# power.net
KiCad netlist of a schematic drawn in Altium Designer
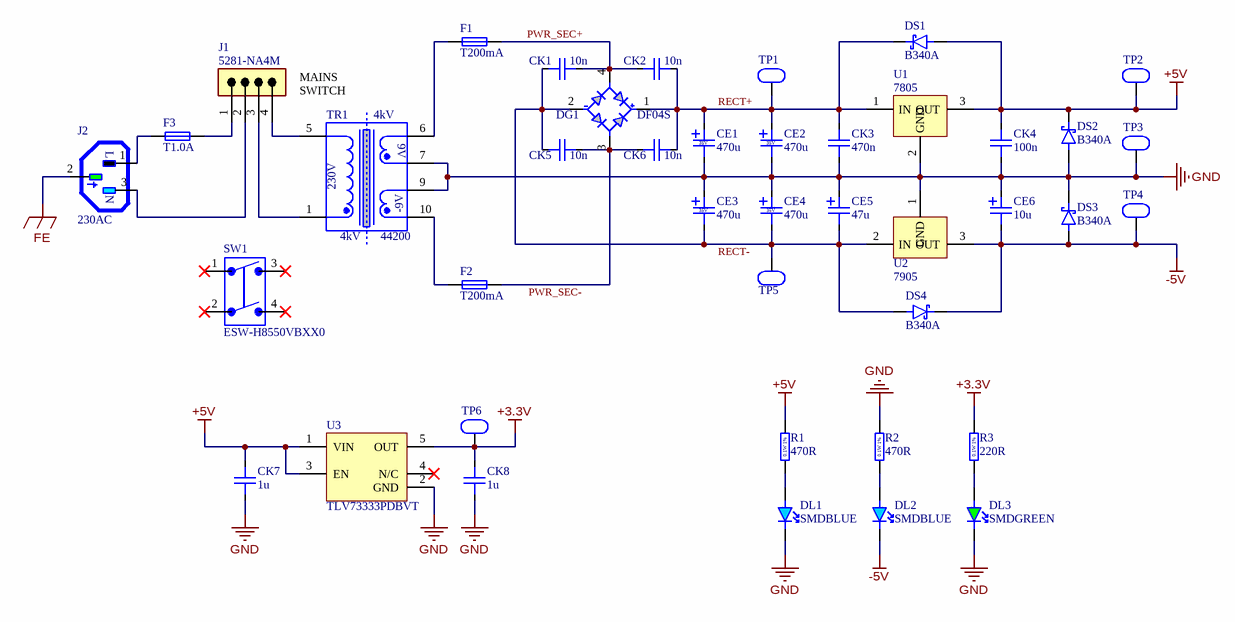
[diagram p0: power.SchDoc]

(export (version "E")
  (design (tool "Eeschema 10.0.6"))
  (components
    (comp (ref "CE1")
      (value "470u")
      (description "C; 470u; 35V; 20%; Aluminum Electrolytic; ??;")
      (fields (field (name "SCH_INFO") "35V"))
      (libsource (lib "") (part "CE_1"))
    )
    (comp (ref "CE2")
      (value "470u")
      (description "C; 470u; 35V; 20%; Aluminum Electrolytic; ??;")
      (fields (field (name "SCH_INFO") "35V"))
      (libsource (lib "") (part "CE_1"))
    )
    (comp (ref "CE3")
      (value "470u")
      (description "C; 470u; 35V; 20%; Aluminum Electrolytic; ??;")
      (fields (field (name "SCH_INFO") "35V"))
      (libsource (lib "") (part "CE_1"))
    )
    (comp (ref "CE4")
      (value "470u")
      (description "C; 470u; 35V; 20%; Aluminum Electrolytic; ??;")
      (fields (field (name "SCH_INFO") "35V"))
      (libsource (lib "") (part "CE_1"))
    )
    (comp (ref "CE5")
      (value "47u")
      (footprint "CAPAE6.8X6.8(D_SIZE)")
      (description "C; 47u; 35V; 20%; Aluminum Electrolytic; ??;")
      (fields (field (name "MANUFACTURER") "Surge, MPN: SVZ21V470M0605V1"))
      (libsource (lib "altium_sql") (part "CE"))
    )
    (comp (ref "CE6")
      (value "10u")
      (footprint "CAPAE5.5X5.5(C_SIZE)")
      (description "C; 10u; 35V; 20%; Aluminum Electrolytic; ??;")
      (fields (field (name "MANUFACTURER") "SAMWHA: SC1V106M05005VR259;;SAMWHA: SC1V106M05005VR289"))
      (libsource (lib "altium_sql") (part "CE"))
    )
    (comp (ref "CK1")
      (value "10n")
      (footprint "CAPC1608X09N(SMC0603)")
      (description "C; 10n; 50V; 5%; NP0/C0G; ??;")
      (fields (field (name "MANUFACTURER") "TDK: C1608C0G1H103J080AA"))
      (libsource (lib "altium_sql") (part "CK"))
    )
    (comp (ref "CK2")
      (value "10n")
      (footprint "CAPC1608X09N(SMC0603)")
      (description "C; 10n; 50V; 5%; NP0/C0G; ??;")
      (fields (field (name "MANUFACTURER") "TDK: C1608C0G1H103J080AA"))
      (libsource (lib "altium_sql") (part "CK"))
    )
    (comp (ref "CK3")
      (value "470n")
      (footprint "CAPC1608X09N(SMC0603)")
      (description "C; 470n; 50V; 10%; X7R; ??;")
      (fields
        (field (name "MANUFACTURER") "TDK: C1608X7R1H474KT-S;;TDK: C1608X7R1H474KT000E;;TDK: C1608X7R1H474K080AC")
      )
      (libsource (lib "altium_sql") (part "CK"))
    )
    (comp (ref "CK4")
      (value "100n")
      (footprint "CAPC1608X09N(SMC0603)")
      (description "C; 100n; 100V; 10%; X7R; ??;")
      (fields
        (field (name "MANUFACTURER") "Murata Electronics: GRM188R72A104KA35D;;Yageo: CC0603KRX7R0BB104")
      )
      (libsource (lib "altium_sql") (part "CK"))
    )
    (comp (ref "CK5")
      (value "10n")
      (footprint "CAPC1608X09N(SMC0603)")
      (description "C; 10n; 50V; 5%; NP0/C0G; ??;")
      (fields (field (name "MANUFACTURER") "TDK: C1608C0G1H103J080AA"))
      (libsource (lib "altium_sql") (part "CK"))
    )
    (comp (ref "CK6")
      (value "10n")
      (footprint "CAPC1608X09N(SMC0603)")
      (description "C; 10n; 50V; 5%; NP0/C0G; ??;")
      (fields (field (name "MANUFACTURER") "TDK: C1608C0G1H103J080AA"))
      (libsource (lib "altium_sql") (part "CK"))
    )
    (comp (ref "CK7")
      (value "1u")
      (footprint "CAPC1608X09N(SMC0603)")
      (description "C; 1u; 50V; 10%; X5R; ??;")
      (libsource (lib "altium_sql") (part "CK"))
    )
    (comp (ref "CK8")
      (value "1u")
      (footprint "CAPC1608X09N(SMC0603)")
      (description "C; 1u; 50V; 10%; X5R; ??;")
      (libsource (lib "altium_sql") (part "CK"))
    )
    (comp (ref "DG1")
      (value "DF04S")
      (footprint "DIP300RM5.08_SMD")
      (description "D; Bridge; 400V; 1A; 1x;")
      (libsource (lib "altium_sql") (part "EDG+DF04SXX0"))
    )
    (comp (ref "DL1")
      (value "SMDBLUE")
      (footprint "DIOC2012X12N(SMLED0805)B")
      (description "Ind; Light; Blue;")
      (fields (field (name "MANUFACTURER") "MULTICOMP: OVS-0803"))
      (libsource (lib "altium_sql") (part "DL_B"))
    )
    (comp (ref "DL2")
      (value "SMDBLUE")
      (footprint "DIOC2012X12N(SMLED0805)B")
      (description "Ind; Light; Blue;")
      (fields (field (name "MANUFACTURER") "MULTICOMP: OVS-0803"))
      (libsource (lib "altium_sql") (part "DL_B"))
    )
    (comp (ref "DL3")
      (value "SMDGREEN")
      (footprint "DIOC2012X12N(SMLED0805)G")
      (description "Ind; Light; Green;")
      (fields (field (name "MANUFACTURER") "HEBEI: 0805KGCT;;BRIGHTLED: BL-HGE35A-AV-TRB"))
      (libsource (lib "altium_sql") (part "DL_G"))
    )
    (comp (ref "DS1")
      (value "B340A")
      (footprint "DIOM5127X23N(SMA)")
      (description "D; Schottky; 40V; 3A; 1x;")
      (fields
        (field (name "MANUFACTURER") "DIODES INC: B340A-13-F;;ONS: MBRA340T3G;;VISHAY: SSA34;;BOURNS: B340LF;;MCC: SK34A-LTP")
      )
      (libsource (lib "altium_sql") (part "DS"))
    )
    (comp (ref "DS2")
      (value "B340A")
      (footprint "DIOM5127X23N(SMA)")
      (description "D; Schottky; 40V; 3A; 1x;")
      (fields
        (field (name "MANUFACTURER") "DIODES INC: B340A-13-F;;ONS: MBRA340T3G;;VISHAY: SSA34;;BOURNS: B340LF;;MCC: SK34A-LTP")
      )
      (libsource (lib "altium_sql") (part "DS"))
    )
    (comp (ref "DS3")
      (value "B340A")
      (footprint "DIOM5127X23N(SMA)")
      (description "D; Schottky; 40V; 3A; 1x;")
      (fields
        (field (name "MANUFACTURER") "DIODES INC: B340A-13-F;;ONS: MBRA340T3G;;VISHAY: SSA34;;BOURNS: B340LF;;MCC: SK34A-LTP")
      )
      (libsource (lib "altium_sql") (part "DS"))
    )
    (comp (ref "DS4")
      (value "B340A")
      (footprint "DIOM5127X23N(SMA)")
      (description "D; Schottky; 40V; 3A; 1x;")
      (fields
        (field (name "MANUFACTURER") "DIODES INC: B340A-13-F;;ONS: MBRA340T3G;;VISHAY: SSA34;;BOURNS: B340LF;;MCC: SK34A-LTP")
      )
      (libsource (lib "altium_sql") (part "DS"))
    )
    (comp (ref "F1")
      (value "T200mA")
      (footprint "FUSE-C8.5")
      (description "CP; Current [A]; 0.2; R:No; 1x;")
      (fields (field (name "MANUFACTURER") "SCHURTER: MST250 0034.6608;;SCHURTER: MST250 0034.6708"))
      (libsource (lib "altium_sql") (part "FUSE_PCB"))
    )
    (comp (ref "F2")
      (value "T200mA")
      (footprint "FUSE-C8.5")
      (description "CP; Current [A]; 0.2; R:No; 1x;")
      (fields (field (name "MANUFACTURER") "SCHURTER: MST250 0034.6608;;SCHURTER: MST250 0034.6708"))
      (libsource (lib "altium_sql") (part "FUSE_PCB"))
    )
    (comp (ref "F3")
      (value "T1.0A")
      (footprint "FUSE-C8.5")
      (description "CP; Current [A]; 1; R:No; 1x;")
      (fields (field (name "MANUFACTURER") "SCHURTER: 34,6615"))
      (libsource (lib "altium_sql") (part "FUSE_PCB"))
    )
    (comp (ref "J1")
      (value "5281-NA4M")
      (footprint "4P-NA-5.08")
      (description "Con; Wire to board RM5.04; 4x; PCB; Straight; 250V; 7A; Male; Tin; ??;")
      (fields
        (field (name "MANUFACTURER") "HSUAN MAO: W4508-04PSYTW0R;;HSM: W4508-04PSYTW0R;;MOLEX: 10-32-1041")
      )
      (libsource (lib "altium_sql") (part "EJ-5281-NA4MX0"))
    )
    (comp (ref "J2")
      (value "230AC")
      (footprint "SCHURTER_GSP1.8501.1")
      (description "Con; AC plug; 1x; PCB; ??; 250V; 10A; Male; Tin; ??;")
      (fields (field (name "MANUFACTURER") "SCHURTER: GSP1.8501.1"))
      (libsource (lib "altium_sql") (part "EJ-GSP1SC1"))
    )
    (comp (ref "R1")
      (value "470R")
      (footprint "RESC1608X06N(SMR0603)")
      (description "R; 470R; 0.1W; 1%; 75V; Thick Film; ±100ppm/K; 1x;")
      (fields
        (field (name "MANUFACTURER") "Yageo: RC0603FR-07470RL;;Panasonic: ERJ3EKF4700V")
        (field (name "SCH_INFO") "0.1W 1%")
      )
      (libsource (lib "altium_sql") (part "R"))
    )
    (comp (ref "R2")
      (value "470R")
      (footprint "RESC1608X06N(SMR0603)")
      (description "R; 470R; 0.1W; 1%; 75V; Thick Film; ±100ppm/K; 1x;")
      (fields
        (field (name "MANUFACTURER") "Yageo: RC0603FR-07470RL;;Panasonic: ERJ3EKF4700V")
        (field (name "SCH_INFO") "0.1W 1%")
      )
      (libsource (lib "altium_sql") (part "R"))
    )
    (comp (ref "R3")
      (value "220R")
      (footprint "RESC1608X06N(SMR0603)")
      (description "R; 220R; 0.1W; 1%; 75V; Thick Film; ±100ppm/K; 1x;")
      (fields (field (name "MANUFACTURER") "VISHAY: CRCW0603220RFKEA") (field (name "SCH_INFO") "0.1W 1%"))
      (libsource (lib "altium_sql") (part "R"))
    )
    (comp (ref "SW1")
      (value "ESW-H8550VBXX0")
      (description "MSw; DPST; Panel; 2x; DC:??V; DC:??A; AC:250V; AC:9A; CV:??V; Switch;")
      (fields (field (name "MANUFACTURER") "SWITRONIC: R19-20.BBBT;;SWITRONIC: R19-20.BBBT+-G"))
      (libsource (lib "altium_sql") (part "ESW-H8550VBXX0"))
    )
    (comp (ref "TP1")
      (value "Test Point")
      (footprint "SMD_Testpoint_Onelayer")
      (description "Con; Test Point; 1x; PCB; ??; ??V; ??A; ??; Tin; Contact;")
      (fields (field (name "MANUFACTURER") "Harwin: S1751-46R") (field (name "CONNECTOR_PART") "Contact"))
      (libsource (lib "altium_sql") (part "EJ+TESTPOINTXX0"))
    )
    (comp (ref "TP2")
      (value "Test Point")
      (footprint "SMD_Testpoint_Onelayer")
      (description "Con; Test Point; 1x; PCB; ??; ??V; ??A; ??; Tin; Contact;")
      (fields (field (name "MANUFACTURER") "Harwin: S1751-46R") (field (name "CONNECTOR_PART") "Contact"))
      (libsource (lib "altium_sql") (part "EJ+TESTPOINTXX0"))
    )
    (comp (ref "TP3")
      (value "Test Point")
      (footprint "SMD_Testpoint_Onelayer")
      (description "Con; Test Point; 1x; PCB; ??; ??V; ??A; ??; Tin; Contact;")
      (fields (field (name "MANUFACTURER") "Harwin: S1751-46R") (field (name "CONNECTOR_PART") "Contact"))
      (libsource (lib "altium_sql") (part "EJ+TESTPOINTXX0"))
    )
    (comp (ref "TP4")
      (value "Test Point")
      (footprint "SMD_Testpoint_Onelayer")
      (description "Con; Test Point; 1x; PCB; ??; ??V; ??A; ??; Tin; Contact;")
      (fields (field (name "MANUFACTURER") "Harwin: S1751-46R") (field (name "CONNECTOR_PART") "Contact"))
      (libsource (lib "altium_sql") (part "EJ+TESTPOINTXX0"))
    )
    (comp (ref "TP5")
      (value "Test Point")
      (footprint "SMD_Testpoint_Onelayer")
      (description "Con; Test Point; 1x; PCB; ??; ??V; ??A; ??; Tin; Contact;")
      (fields (field (name "MANUFACTURER") "Harwin: S1751-46R") (field (name "CONNECTOR_PART") "Contact"))
      (libsource (lib "altium_sql") (part "EJ+TESTPOINTXX0"))
    )
    (comp (ref "TP6")
      (value "Test Point")
      (footprint "SMD_Testpoint_Onelayer")
      (description "Con; Test Point; 1x; PCB; ??; ??V; ??A; ??; Tin; Contact;")
      (fields (field (name "MANUFACTURER") "Harwin: S1751-46R") (field (name "CONNECTOR_PART") "Contact"))
      (libsource (lib "altium_sql") (part "EJ+TESTPOINTXX0"))
    )
    (comp (ref "TR1")
      (value "44200")
      (footprint "44200")
      (description "Transformer 230V/2x9V, 2x178mA")
      (libsource (lib "custom-footprints") (part "44200"))
    )
    (comp (ref "U1")
      (value "7805")
      (footprint "DPAK254P1544X483-3N(D2PAK)")
      (description "Fixed, Three Terminal Pos  Regulator 5V/1A in D2PAK")
      (libsource (lib "custom-footprints") (part "L7805AC"))
    )
    (comp (ref "U2")
      (value "7905")
      (footprint "DPAK254P1544X483-3N(D2PAK)")
      (description "Fixed, Three Terminal Pos  Regulator -5V/1A in D2PAK")
      (libsource (lib "custom-footprints") (part "L7905AC"))
    )
    (comp (ref "U3")
      (value "TLV73333PDBVT")
      (footprint "SOT95P280X145-5N(SOT23-5)")
      (description "IC; Linear Regulator/Reference; ??V; 5.5V; 1x;")
      (fields (field (name "MANUFACTURER") "Texas Instruments: TLV73333PDBVT"))
      (libsource (lib "altium_sql") (part "EU+NCV8702SN18XX0"))
    )
  )
  (nets
    (net (code "1") (name "+3.3V") (class "Default")
      (node (ref "CK8") (pin "1") (pinfunction "1_1") (pintype "passive"))
      (node (ref "R3") (pin "2") (pinfunction "2_2") (pintype "passive"))
      (node (ref "TP6") (pin "1") (pintype "passive"))
      (node (ref "U3") (pin "5") (pinfunction "OUT_5") (pintype "power_in"))
    )
    (net (code "2") (name "+5V") (class "Default")
      (node (ref "CK4") (pin "1") (pinfunction "1_1") (pintype "passive"))
      (node (ref "CK7") (pin "1") (pinfunction "1_1") (pintype "passive"))
      (node (ref "DS1") (pin "2") (pinfunction "A_2") (pintype "passive"))
      (node (ref "DS2") (pin "1") (pinfunction "C_1") (pintype "passive"))
      (node (ref "R1") (pin "2") (pinfunction "2_2") (pintype "passive"))
      (node (ref "TP2") (pin "1") (pintype "passive"))
      (node (ref "U1") (pin "3") (pinfunction "OUT_3") (pintype "passive"))
      (node (ref "U3") (pin "1") (pinfunction "VIN_1") (pintype "power_in"))
      (node (ref "U3") (pin "3") (pinfunction "EN_3") (pintype "passive"))
    )
    (net (code "3") (name "-5V") (class "Default")
      (node (ref "CE6") (pin "2") (pinfunction "2_2") (pintype "passive"))
      (node (ref "DL2") (pin "1") (pinfunction "C_1") (pintype "passive"))
      (node (ref "DS3") (pin "2") (pinfunction "A_2") (pintype "passive"))
      (node (ref "DS4") (pin "1") (pinfunction "C_1") (pintype "passive"))
      (node (ref "TP4") (pin "1") (pintype "passive"))
      (node (ref "U2") (pin "3") (pinfunction "OUT_3") (pintype "passive"))
    )
    (net (code "4") (name "/PWR_SEC+") (class "Default")
      (node (ref "CK1") (pin "2") (pinfunction "2_2") (pintype "passive"))
      (node (ref "CK2") (pin "1") (pinfunction "1_1") (pintype "passive"))
      (node (ref "DG1") (pin "4") (pinfunction "AC_4") (pintype "passive"))
      (node (ref "F1") (pin "2") (pintype "passive"))
    )
    (net (code "5") (name "/PWR_SEC-") (class "Default")
      (node (ref "CK5") (pin "2") (pinfunction "2_2") (pintype "passive"))
      (node (ref "CK6") (pin "1") (pinfunction "1_1") (pintype "passive"))
      (node (ref "DG1") (pin "3") (pinfunction "AC_3") (pintype "passive"))
      (node (ref "F2") (pin "2") (pintype "passive"))
    )
    (net (code "6") (name "/RECT+") (class "Default")
      (node (ref "CE1") (pin "1") (pinfunction "1_1") (pintype "passive"))
      (node (ref "CE2") (pin "1") (pinfunction "1_1") (pintype "passive"))
      (node (ref "CK2") (pin "2") (pinfunction "2_2") (pintype "passive"))
      (node (ref "CK3") (pin "1") (pinfunction "1_1") (pintype "passive"))
      (node (ref "CK6") (pin "2") (pinfunction "2_2") (pintype "passive"))
      (node (ref "DG1") (pin "1") (pinfunction "+_1") (pintype "passive"))
      (node (ref "DS1") (pin "1") (pinfunction "C_1") (pintype "passive"))
      (node (ref "TP1") (pin "1") (pintype "passive"))
      (node (ref "U1") (pin "1") (pinfunction "IN_1") (pintype "passive"))
    )
    (net (code "7") (name "/RECT-") (class "Default")
      (node (ref "CE3") (pin "2") (pinfunction "2_2") (pintype "passive"))
      (node (ref "CE4") (pin "2") (pinfunction "2_2") (pintype "passive"))
      (node (ref "CE5") (pin "2") (pinfunction "2_2") (pintype "passive"))
      (node (ref "CK1") (pin "1") (pinfunction "1_1") (pintype "passive"))
      (node (ref "CK5") (pin "1") (pinfunction "1_1") (pintype "passive"))
      (node (ref "DG1") (pin "2") (pinfunction "-_2") (pintype "passive"))
      (node (ref "DS4") (pin "2") (pinfunction "A_2") (pintype "passive"))
      (node (ref "TP5") (pin "1") (pintype "passive"))
      (node (ref "U2") (pin "2") (pinfunction "IN_2") (pintype "passive"))
    )
    (net (code "8") (name "FE") (class "Default") (node (ref "J2") (pin "2") (pintype "passive")))
    (net (code "9") (name "GND") (class "Default")
      (node (ref "CE1") (pin "2") (pinfunction "2_2") (pintype "passive"))
      (node (ref "CE2") (pin "2") (pinfunction "2_2") (pintype "passive"))
      (node (ref "CE3") (pin "1") (pinfunction "1_1") (pintype "passive"))
      (node (ref "CE4") (pin "1") (pinfunction "1_1") (pintype "passive"))
      (node (ref "CE5") (pin "1") (pinfunction "1_1") (pintype "passive"))
      (node (ref "CE6") (pin "1") (pinfunction "1_1") (pintype "passive"))
      (node (ref "CK3") (pin "2") (pinfunction "2_2") (pintype "passive"))
      (node (ref "CK4") (pin "2") (pinfunction "2_2") (pintype "passive"))
      (node (ref "CK7") (pin "2") (pinfunction "2_2") (pintype "passive"))
      (node (ref "CK8") (pin "2") (pinfunction "2_2") (pintype "passive"))
      (node (ref "DL1") (pin "1") (pinfunction "C_1") (pintype "passive"))
      (node (ref "DL3") (pin "1") (pinfunction "C_1") (pintype "passive"))
      (node (ref "DS2") (pin "2") (pinfunction "A_2") (pintype "passive"))
      (node (ref "DS3") (pin "1") (pinfunction "C_1") (pintype "passive"))
      (node (ref "R2") (pin "2") (pinfunction "2_2") (pintype "passive"))
      (node (ref "TP3") (pin "1") (pintype "passive"))
      (node (ref "TR1") (pin "7") (pintype "power_in"))
      (node (ref "TR1") (pin "9") (pintype "power_in"))
      (node (ref "U1") (pin "2") (pinfunction "GND_2") (pintype "passive"))
      (node (ref "U2") (pin "1") (pinfunction "GND_1") (pintype "passive"))
      (node (ref "U3") (pin "2") (pinfunction "GND_2") (pintype "power_in"))
    )
    (net (code "10") (name "Net-(DL1-A)") (class "Default")
      (node (ref "DL1") (pin "2") (pinfunction "A_2") (pintype "passive"))
      (node (ref "R1") (pin "1") (pinfunction "1_1") (pintype "passive"))
    )
    (net (code "11") (name "Net-(DL2-A)") (class "Default")
      (node (ref "DL2") (pin "2") (pinfunction "A_2") (pintype "passive"))
      (node (ref "R2") (pin "1") (pinfunction "1_1") (pintype "passive"))
    )
    (net (code "12") (name "Net-(DL3-A)") (class "Default")
      (node (ref "DL3") (pin "2") (pinfunction "A_2") (pintype "passive"))
      (node (ref "R3") (pin "1") (pinfunction "1_1") (pintype "passive"))
    )
    (net (code "13") (name "Net-(F1-Pad1)") (class "Default")
      (node (ref "F1") (pin "1") (pintype "passive"))
      (node (ref "TR1") (pin "6") (pintype "power_in"))
    )
    (net (code "14") (name "Net-(F2-Pad1)") (class "Default")
      (node (ref "F2") (pin "1") (pintype "passive"))
      (node (ref "TR1") (pin "10") (pintype "power_in"))
    )
    (net (code "15") (name "Net-(F3-Pad1)") (class "Default")
      (node (ref "F3") (pin "1") (pintype "passive"))
      (node (ref "J2") (pin "1") (pintype "passive"))
    )
    (net (code "16") (name "Net-(F3-Pad2)") (class "Default")
      (node (ref "F3") (pin "2") (pintype "passive"))
      (node (ref "J1") (pin "1") (pinfunction "1_1") (pintype "passive"))
    )
    (net (code "17") (name "Net-(J1-4)") (class "Default")
      (node (ref "J1") (pin "3") (pinfunction "4_3") (pintype "passive"))
      (node (ref "TR1") (pin "1") (pintype "power_in"))
    )
    (net (code "18") (name "Net-(J1-6)") (class "Default")
      (node (ref "J1") (pin "4") (pinfunction "6_4") (pintype "passive"))
      (node (ref "TR1") (pin "5") (pintype "power_in"))
    )
    (net (code "19") (name "Net-(J1-Pad2)") (class "Default")
      (node (ref "J1") (pin "2") (pinfunction "2_2") (pintype "passive"))
      (node (ref "J2") (pin "3") (pintype "passive"))
    )
    (net (code "20") (name "unconnected-(SW1-Pad1)") (class "Default")
      (node (ref "SW1") (pin "1") (pintype "passive+no_connect"))
    )
    (net (code "21") (name "unconnected-(SW1-Pad2)") (class "Default")
      (node (ref "SW1") (pin "2") (pintype "passive+no_connect"))
    )
    (net (code "22") (name "unconnected-(SW1-Pad3)") (class "Default")
      (node (ref "SW1") (pin "3") (pintype "passive+no_connect"))
    )
    (net (code "23") (name "unconnected-(SW1-Pad4)") (class "Default")
      (node (ref "SW1") (pin "4") (pintype "passive+no_connect"))
    )
    (net (code "24") (name "unconnected-(U3-N{slash}C-Pad4)") (class "Default")
      (node (ref "U3") (pin "4") (pinfunction "N/C_4") (pintype "power_in+no_connect"))
    )
  )
)
